# trainer.net
KiCad netlist of a schematic drawn in EAGLE
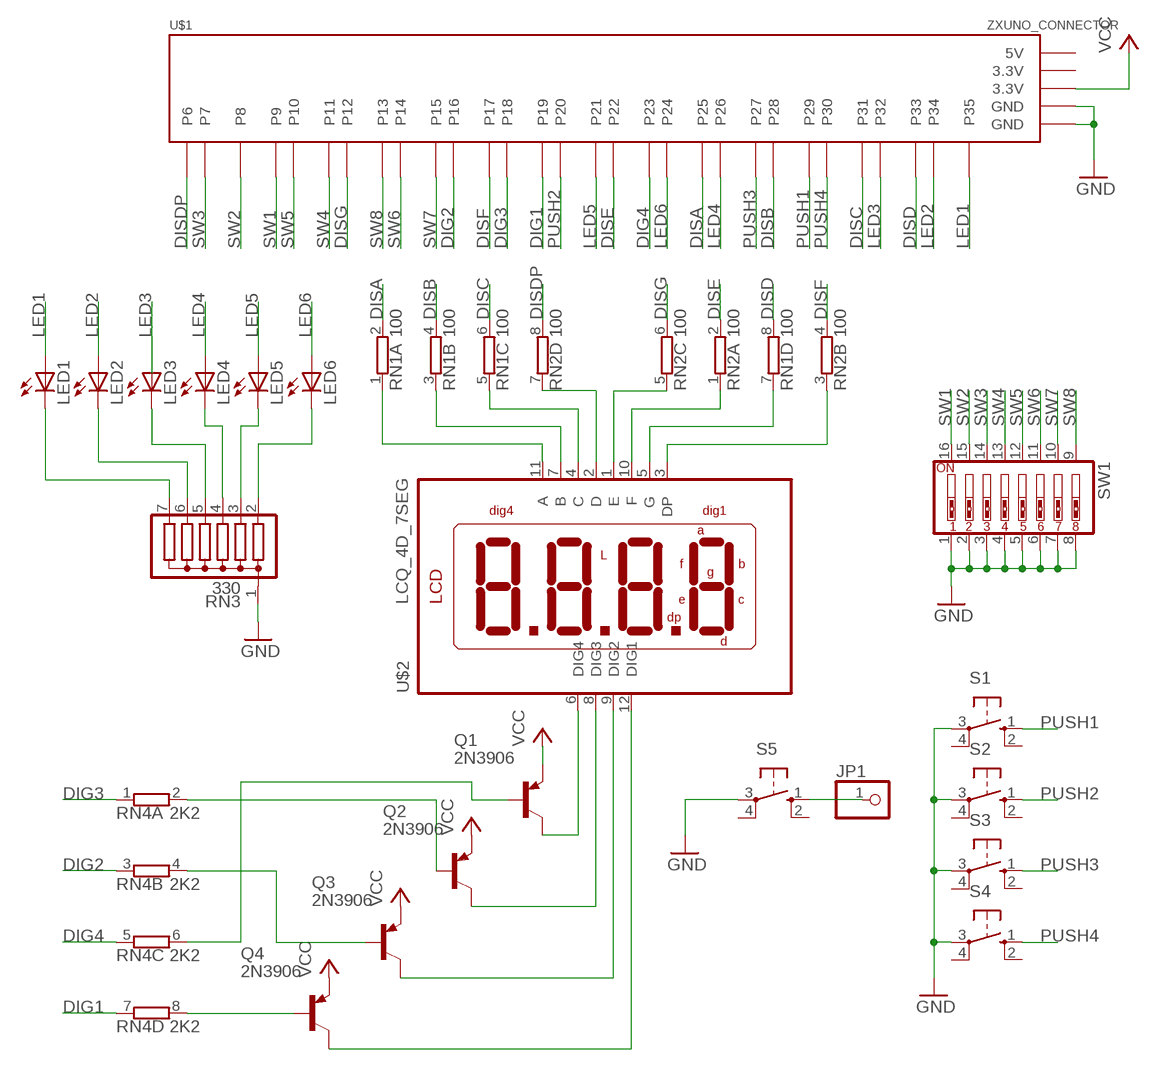
[diagram p0: schematic, sheet 1]

(export (version "E")
  (design (tool "Eeschema 10.0.6"))
  (components
    (comp (ref "JP1")
      (value "PINHD-1X1")
      (footprint "eagle-import:1X01")
      (libsource (lib "eagle-import") (part "PINHD-1X1"))
    )
    (comp (ref "LED1")
      (value "LED3MM")
      (footprint "eagle-import:LED3MM")
      (libsource (lib "eagle-import") (part "LED3MM"))
    )
    (comp (ref "LED2")
      (value "LED3MM")
      (footprint "eagle-import:LED3MM")
      (libsource (lib "eagle-import") (part "LED3MM"))
    )
    (comp (ref "LED3")
      (value "LED3MM")
      (footprint "eagle-import:LED3MM")
      (libsource (lib "eagle-import") (part "LED3MM"))
    )
    (comp (ref "LED4")
      (value "LED3MM")
      (footprint "eagle-import:LED3MM")
      (libsource (lib "eagle-import") (part "LED3MM"))
    )
    (comp (ref "LED5")
      (value "LED3MM")
      (footprint "eagle-import:LED3MM")
      (libsource (lib "eagle-import") (part "LED3MM"))
    )
    (comp (ref "LED6")
      (value "LED3MM")
      (footprint "eagle-import:LED3MM")
      (libsource (lib "eagle-import") (part "LED3MM"))
    )
    (comp (ref "Q1")
      (value "2N3906")
      (footprint "eagle-import:TO92")
      (libsource (lib "eagle-import") (part "2N3906"))
    )
    (comp (ref "Q2")
      (value "2N3906")
      (footprint "eagle-import:TO92")
      (libsource (lib "eagle-import") (part "2N3906"))
    )
    (comp (ref "Q3")
      (value "2N3906")
      (footprint "eagle-import:TO92")
      (libsource (lib "eagle-import") (part "2N3906"))
    )
    (comp (ref "Q4")
      (value "2N3906")
      (footprint "eagle-import:TO92")
      (libsource (lib "eagle-import") (part "2N3906"))
    )
    (comp (ref "RN1")
      (value "100")
      (footprint "eagle-import:SIL8")
      (libsource (lib "eagle-import") (part "E4R"))
    )
    (comp (ref "RN2")
      (value "100")
      (footprint "eagle-import:SIL8")
      (libsource (lib "eagle-import") (part "E4R"))
    )
    (comp (ref "RN3")
      (value "330")
      (footprint "eagle-import:SIL7")
      (libsource (lib "eagle-import") (part "G06R"))
    )
    (comp (ref "RN4")
      (value "2K2")
      (footprint "eagle-import:SIL8")
      (libsource (lib "eagle-import") (part "E4R"))
    )
    (comp (ref "S1")
      (value "10-XX")
      (footprint "eagle-import:B3F-10XX")
      (fields (field (name "MPN") "B3F-1000"))
      (libsource (lib "eagle-import") (part "10-XX"))
    )
    (comp (ref "S2")
      (value "10-XX")
      (footprint "eagle-import:B3F-10XX")
      (fields (field (name "MPN") "B3F-1000"))
      (libsource (lib "eagle-import") (part "10-XX"))
    )
    (comp (ref "S3")
      (value "10-XX")
      (footprint "eagle-import:B3F-10XX")
      (fields (field (name "MPN") "B3F-1000"))
      (libsource (lib "eagle-import") (part "10-XX"))
    )
    (comp (ref "S4")
      (value "10-XX")
      (footprint "eagle-import:B3F-10XX")
      (fields (field (name "MPN") "B3F-1000"))
      (libsource (lib "eagle-import") (part "10-XX"))
    )
    (comp (ref "S5")
      (value "10-XX")
      (footprint "eagle-import:B3F-10XX")
      (fields (field (name "MPN") "B3F-1000"))
      (libsource (lib "eagle-import") (part "10-XX"))
    )
    (comp (ref "SW1")
      (value "SW_DIP-8")
      (footprint "eagle-import:EDG-08")
      (libsource (lib "eagle-import") (part "SW_DIP-8"))
    )
    (comp (ref "U$1")
      (value "ZXUNO_CONNECTOR")
      (footprint "eagle-import:ZXUNO_CONNECTOR")
      (libsource (lib "eagle-import") (part "ZXUNO_CONNECTOR"))
    )
    (comp (ref "U$2")
      (value "LCQ_4D_7SEG")
      (footprint "eagle-import:LDQ_4D_7SEG")
      (libsource (lib "eagle-import") (part "LCQ_4D_7SEG"))
    )
  )
  (nets
    (net (code "1") (name "/3.3V") (class "Default")
      (node (ref "U$1") (pin "3.3V@1") (pinfunction "3.3V_3.3V@1") (pintype "power_in"))
    )
    (net (code "2") (name "/5V") (class "Default")
      (node (ref "U$1") (pin "5V") (pinfunction "5V_5V") (pintype "power_in"))
    )
    (net (code "3") (name "/DIG1") (class "Default")
      (node (ref "RN4") (pin "7") (pinfunction "1_7") (pintype "passive"))
      (node (ref "U$1") (pin "P19") (pinfunction "P19_P19") (pintype "bidirectional"))
    )
    (net (code "4") (name "/DIG2") (class "Default")
      (node (ref "RN4") (pin "3") (pinfunction "1_3") (pintype "passive"))
      (node (ref "U$1") (pin "P16") (pinfunction "P16_P16") (pintype "bidirectional"))
    )
    (net (code "5") (name "/DIG3") (class "Default")
      (node (ref "RN4") (pin "1") (pinfunction "1_1") (pintype "passive"))
      (node (ref "U$1") (pin "P18") (pinfunction "P18_P18") (pintype "bidirectional"))
    )
    (net (code "6") (name "/DIG4") (class "Default")
      (node (ref "RN4") (pin "5") (pinfunction "1_5") (pintype "passive"))
      (node (ref "U$1") (pin "P23") (pinfunction "P23_P23") (pintype "bidirectional"))
    )
    (net (code "7") (name "/DISA") (class "Default")
      (node (ref "RN1") (pin "2") (pinfunction "2_2") (pintype "passive"))
      (node (ref "U$1") (pin "P25") (pinfunction "P25_P25") (pintype "bidirectional"))
    )
    (net (code "8") (name "/DISB") (class "Default")
      (node (ref "RN1") (pin "4") (pinfunction "2_4") (pintype "passive"))
      (node (ref "U$1") (pin "P28") (pinfunction "P28_P28") (pintype "bidirectional"))
    )
    (net (code "9") (name "/DISC") (class "Default")
      (node (ref "RN1") (pin "6") (pinfunction "2_6") (pintype "passive"))
      (node (ref "U$1") (pin "P31") (pinfunction "P31_P31") (pintype "bidirectional"))
    )
    (net (code "10") (name "/DISD") (class "Default")
      (node (ref "RN1") (pin "8") (pinfunction "2_8") (pintype "passive"))
      (node (ref "U$1") (pin "P33") (pinfunction "P33_P33") (pintype "bidirectional"))
    )
    (net (code "11") (name "/DISDP") (class "Default")
      (node (ref "RN2") (pin "8") (pinfunction "2_8") (pintype "passive"))
      (node (ref "U$1") (pin "P6") (pinfunction "P6_P6") (pintype "bidirectional"))
    )
    (net (code "12") (name "/DISE") (class "Default")
      (node (ref "RN2") (pin "2") (pinfunction "2_2") (pintype "passive"))
      (node (ref "U$1") (pin "P22") (pinfunction "P22_P22") (pintype "bidirectional"))
    )
    (net (code "13") (name "/DISF") (class "Default")
      (node (ref "RN2") (pin "4") (pinfunction "2_4") (pintype "passive"))
      (node (ref "U$1") (pin "P17") (pinfunction "P17_P17") (pintype "bidirectional"))
    )
    (net (code "14") (name "/DISG") (class "Default")
      (node (ref "RN2") (pin "6") (pinfunction "2_6") (pintype "passive"))
      (node (ref "U$1") (pin "P12") (pinfunction "P12_P12") (pintype "bidirectional"))
    )
    (net (code "15") (name "/LED1") (class "Default")
      (node (ref "LED1") (pin "A") (pinfunction "A_A") (pintype "passive"))
      (node (ref "U$1") (pin "P35") (pinfunction "P35_P35") (pintype "bidirectional"))
    )
    (net (code "16") (name "/LED2") (class "Default")
      (node (ref "LED2") (pin "A") (pinfunction "A_A") (pintype "passive"))
      (node (ref "U$1") (pin "P34") (pinfunction "P34_P34") (pintype "bidirectional"))
    )
    (net (code "17") (name "/LED3") (class "Default")
      (node (ref "LED3") (pin "A") (pinfunction "A_A") (pintype "passive"))
      (node (ref "U$1") (pin "P32") (pinfunction "P32_P32") (pintype "bidirectional"))
    )
    (net (code "18") (name "/LED4") (class "Default")
      (node (ref "LED4") (pin "A") (pinfunction "A_A") (pintype "passive"))
      (node (ref "U$1") (pin "P26") (pinfunction "P26_P26") (pintype "bidirectional"))
    )
    (net (code "19") (name "/LED5") (class "Default")
      (node (ref "LED5") (pin "A") (pinfunction "A_A") (pintype "passive"))
      (node (ref "U$1") (pin "P21") (pinfunction "P21_P21") (pintype "bidirectional"))
    )
    (net (code "20") (name "/LED6") (class "Default")
      (node (ref "LED6") (pin "A") (pinfunction "A_A") (pintype "passive"))
      (node (ref "U$1") (pin "P24") (pinfunction "P24_P24") (pintype "bidirectional"))
    )
    (net (code "21") (name "/PUSH1") (class "Default")
      (node (ref "S1") (pin "1") (pinfunction "S_1") (pintype "passive"))
      (node (ref "U$1") (pin "P29") (pinfunction "P29_P29") (pintype "bidirectional"))
    )
    (net (code "22") (name "/PUSH2") (class "Default")
      (node (ref "S2") (pin "1") (pinfunction "S_1") (pintype "passive"))
      (node (ref "U$1") (pin "P20") (pinfunction "P20_P20") (pintype "bidirectional"))
    )
    (net (code "23") (name "/PUSH3") (class "Default")
      (node (ref "S3") (pin "1") (pinfunction "S_1") (pintype "passive"))
      (node (ref "U$1") (pin "P27") (pinfunction "P27_P27") (pintype "bidirectional"))
    )
    (net (code "24") (name "/PUSH4") (class "Default")
      (node (ref "S4") (pin "1") (pinfunction "S_1") (pintype "passive"))
      (node (ref "U$1") (pin "P30") (pinfunction "P30_P30") (pintype "bidirectional"))
    )
    (net (code "25") (name "/SW1") (class "Default")
      (node (ref "SW1") (pin "16") (pinfunction "16_16") (pintype "passive"))
      (node (ref "U$1") (pin "P9") (pinfunction "P9_P9") (pintype "bidirectional"))
    )
    (net (code "26") (name "/SW2") (class "Default")
      (node (ref "SW1") (pin "15") (pinfunction "15_15") (pintype "passive"))
      (node (ref "U$1") (pin "P8") (pinfunction "P8_P8") (pintype "bidirectional"))
    )
    (net (code "27") (name "/SW3") (class "Default")
      (node (ref "SW1") (pin "14") (pinfunction "14_14") (pintype "passive"))
      (node (ref "U$1") (pin "P7") (pinfunction "P7_P7") (pintype "bidirectional"))
    )
    (net (code "28") (name "/SW4") (class "Default")
      (node (ref "SW1") (pin "13") (pinfunction "13_13") (pintype "passive"))
      (node (ref "U$1") (pin "P11") (pinfunction "P11_P11") (pintype "bidirectional"))
    )
    (net (code "29") (name "/SW5") (class "Default")
      (node (ref "SW1") (pin "12") (pinfunction "12_12") (pintype "passive"))
      (node (ref "U$1") (pin "P10") (pinfunction "P10_P10") (pintype "bidirectional"))
    )
    (net (code "30") (name "/SW6") (class "Default")
      (node (ref "SW1") (pin "11") (pinfunction "11_11") (pintype "passive"))
      (node (ref "U$1") (pin "P14") (pinfunction "P14_P14") (pintype "bidirectional"))
    )
    (net (code "31") (name "/SW7") (class "Default")
      (node (ref "SW1") (pin "10") (pinfunction "10_10") (pintype "passive"))
      (node (ref "U$1") (pin "P15") (pinfunction "P15_P15") (pintype "bidirectional"))
    )
    (net (code "32") (name "/SW8") (class "Default")
      (node (ref "SW1") (pin "9") (pinfunction "9_9") (pintype "passive"))
      (node (ref "U$1") (pin "P13") (pinfunction "P13_P13") (pintype "bidirectional"))
    )
    (net (code "33") (name "GND") (class "Default")
      (node (ref "RN3") (pin "1") (pinfunction "1_1") (pintype "passive"))
      (node (ref "S1") (pin "3") (pinfunction "P_3") (pintype "passive"))
      (node (ref "S2") (pin "3") (pinfunction "P_3") (pintype "passive"))
      (node (ref "S3") (pin "3") (pinfunction "P_3") (pintype "passive"))
      (node (ref "S4") (pin "3") (pinfunction "P_3") (pintype "passive"))
      (node (ref "S5") (pin "3") (pinfunction "P_3") (pintype "passive"))
      (node (ref "SW1") (pin "1") (pinfunction "1_1") (pintype "passive"))
      (node (ref "SW1") (pin "2") (pinfunction "2_2") (pintype "passive"))
      (node (ref "SW1") (pin "3") (pinfunction "3_3") (pintype "passive"))
      (node (ref "SW1") (pin "4") (pinfunction "4_4") (pintype "passive"))
      (node (ref "SW1") (pin "5") (pinfunction "5_5") (pintype "passive"))
      (node (ref "SW1") (pin "6") (pinfunction "6_6") (pintype "passive"))
      (node (ref "SW1") (pin "7") (pinfunction "7_7") (pintype "passive"))
      (node (ref "SW1") (pin "8") (pinfunction "8_8") (pintype "passive"))
      (node (ref "U$1") (pin "GND@1") (pinfunction "GND_GND@1") (pintype "power_in"))
      (node (ref "U$1") (pin "GND@2") (pinfunction "GND_GND@2") (pintype "power_in"))
    )
    (net (code "34") (name "Net-(LED1-C)") (class "Default")
      (node (ref "LED1") (pin "K") (pinfunction "C_K") (pintype "passive"))
      (node (ref "RN3") (pin "7") (pinfunction "7_7") (pintype "passive"))
    )
    (net (code "35") (name "Net-(LED2-C)") (class "Default")
      (node (ref "LED2") (pin "K") (pinfunction "C_K") (pintype "passive"))
      (node (ref "RN3") (pin "6") (pinfunction "6_6") (pintype "passive"))
    )
    (net (code "36") (name "Net-(LED3-C)") (class "Default")
      (node (ref "LED3") (pin "K") (pinfunction "C_K") (pintype "passive"))
      (node (ref "RN3") (pin "5") (pinfunction "5_5") (pintype "passive"))
    )
    (net (code "37") (name "Net-(LED4-C)") (class "Default")
      (node (ref "LED4") (pin "K") (pinfunction "C_K") (pintype "passive"))
      (node (ref "RN3") (pin "4") (pinfunction "4_4") (pintype "passive"))
    )
    (net (code "38") (name "Net-(LED5-C)") (class "Default")
      (node (ref "LED5") (pin "K") (pinfunction "C_K") (pintype "passive"))
      (node (ref "RN3") (pin "3") (pinfunction "3_3") (pintype "passive"))
    )
    (net (code "39") (name "Net-(LED6-C)") (class "Default")
      (node (ref "LED6") (pin "K") (pinfunction "C_K") (pintype "passive"))
      (node (ref "RN3") (pin "2") (pinfunction "2_2") (pintype "passive"))
    )
    (net (code "40") (name "Net-(Q1-B)") (class "Default")
      (node (ref "Q1") (pin "2") (pinfunction "B_2") (pintype "passive"))
      (node (ref "RN4") (pin "6") (pinfunction "2_6") (pintype "passive"))
    )
    (net (code "41") (name "Net-(Q1-C)") (class "Default")
      (node (ref "Q1") (pin "1") (pinfunction "C_1") (pintype "passive"))
      (node (ref "U$2") (pin "6") (pinfunction "DIG4_6") (pintype "input"))
    )
    (net (code "42") (name "Net-(Q2-B)") (class "Default")
      (node (ref "Q2") (pin "2") (pinfunction "B_2") (pintype "passive"))
      (node (ref "RN4") (pin "2") (pinfunction "2_2") (pintype "passive"))
    )
    (net (code "43") (name "Net-(Q2-C)") (class "Default")
      (node (ref "Q2") (pin "1") (pinfunction "C_1") (pintype "passive"))
      (node (ref "U$2") (pin "8") (pinfunction "DIG3_8") (pintype "input"))
    )
    (net (code "44") (name "Net-(Q3-B)") (class "Default")
      (node (ref "Q3") (pin "2") (pinfunction "B_2") (pintype "passive"))
      (node (ref "RN4") (pin "4") (pinfunction "2_4") (pintype "passive"))
    )
    (net (code "45") (name "Net-(Q3-C)") (class "Default")
      (node (ref "Q3") (pin "1") (pinfunction "C_1") (pintype "passive"))
      (node (ref "U$2") (pin "9") (pinfunction "DIG2_9") (pintype "input"))
    )
    (net (code "46") (name "Net-(Q4-B)") (class "Default")
      (node (ref "Q4") (pin "2") (pinfunction "B_2") (pintype "passive"))
      (node (ref "RN4") (pin "8") (pinfunction "2_8") (pintype "passive"))
    )
    (net (code "47") (name "Net-(Q4-C)") (class "Default")
      (node (ref "Q4") (pin "1") (pinfunction "C_1") (pintype "passive"))
      (node (ref "U$2") (pin "12") (pinfunction "DIG1_12") (pintype "input"))
    )
    (net (code "48") (name "Net-(RN1B-1)") (class "Default")
      (node (ref "RN1") (pin "3") (pinfunction "1_3") (pintype "passive"))
      (node (ref "U$2") (pin "7") (pinfunction "B_7") (pintype "input"))
    )
    (net (code "49") (name "Net-(RN1C-1)") (class "Default")
      (node (ref "RN1") (pin "5") (pinfunction "1_5") (pintype "passive"))
      (node (ref "U$2") (pin "4") (pinfunction "C_4") (pintype "input"))
    )
    (net (code "50") (name "Net-(RN1D-1)") (class "Default")
      (node (ref "RN1") (pin "7") (pinfunction "1_7") (pintype "passive"))
      (node (ref "U$2") (pin "5") (pinfunction "G_5") (pintype "input"))
    )
    (net (code "51") (name "Net-(RN2B-1)") (class "Default")
      (node (ref "RN2") (pin "3") (pinfunction "1_3") (pintype "passive"))
      (node (ref "U$2") (pin "3") (pinfunction "DP_3") (pintype "input"))
    )
    (net (code "52") (name "Net-(RN2C-1)") (class "Default")
      (node (ref "RN2") (pin "5") (pinfunction "1_5") (pintype "passive"))
      (node (ref "U$2") (pin "1") (pinfunction "E_1") (pintype "input"))
    )
    (net (code "53") (name "Net-(RN2D-1)") (class "Default")
      (node (ref "RN2") (pin "7") (pinfunction "1_7") (pintype "passive"))
      (node (ref "U$2") (pin "2") (pinfunction "D_2") (pintype "input"))
    )
    (net (code "54") (name "Net-(S5-S)") (class "Default")
      (node (ref "JP1") (pin "1") (pinfunction "1_1") (pintype "passive"))
      (node (ref "S5") (pin "1") (pinfunction "S_1") (pintype "passive"))
    )
    (net (code "55") (name "Net-(U$2-A)") (class "Default")
      (node (ref "RN1") (pin "1") (pinfunction "1_1") (pintype "passive"))
      (node (ref "U$2") (pin "11") (pinfunction "A_11") (pintype "input"))
    )
    (net (code "56") (name "Net-(U$2-F)") (class "Default")
      (node (ref "RN2") (pin "1") (pinfunction "1_1") (pintype "passive"))
      (node (ref "U$2") (pin "10") (pinfunction "F_10") (pintype "input"))
    )
    (net (code "57") (name "VCC") (class "Default")
      (node (ref "Q1") (pin "3") (pinfunction "E_3") (pintype "passive"))
      (node (ref "Q2") (pin "3") (pinfunction "E_3") (pintype "passive"))
      (node (ref "Q3") (pin "3") (pinfunction "E_3") (pintype "passive"))
      (node (ref "Q4") (pin "3") (pinfunction "E_3") (pintype "passive"))
      (node (ref "U$1") (pin "3.3V@2") (pinfunction "3.3V_3.3V@2") (pintype "power_in"))
    )
    (net (code "58") (name "unconnected-(S1-P1-Pad4)") (class "Default")
      (node (ref "S1") (pin "4") (pinfunction "P1_4") (pintype "passive"))
    )
    (net (code "59") (name "unconnected-(S1-S1-Pad2)") (class "Default")
      (node (ref "S1") (pin "2") (pinfunction "S1_2") (pintype "passive"))
    )
    (net (code "60") (name "unconnected-(S2-P1-Pad4)") (class "Default")
      (node (ref "S2") (pin "4") (pinfunction "P1_4") (pintype "passive"))
    )
    (net (code "61") (name "unconnected-(S2-S1-Pad2)") (class "Default")
      (node (ref "S2") (pin "2") (pinfunction "S1_2") (pintype "passive"))
    )
    (net (code "62") (name "unconnected-(S3-P1-Pad4)") (class "Default")
      (node (ref "S3") (pin "4") (pinfunction "P1_4") (pintype "passive"))
    )
    (net (code "63") (name "unconnected-(S3-S1-Pad2)") (class "Default")
      (node (ref "S3") (pin "2") (pinfunction "S1_2") (pintype "passive"))
    )
    (net (code "64") (name "unconnected-(S4-P1-Pad4)") (class "Default")
      (node (ref "S4") (pin "4") (pinfunction "P1_4") (pintype "passive"))
    )
    (net (code "65") (name "unconnected-(S4-S1-Pad2)") (class "Default")
      (node (ref "S4") (pin "2") (pinfunction "S1_2") (pintype "passive"))
    )
    (net (code "66") (name "unconnected-(S5-P1-Pad4)") (class "Default")
      (node (ref "S5") (pin "4") (pinfunction "P1_4") (pintype "passive"))
    )
    (net (code "67") (name "unconnected-(S5-S1-Pad2)") (class "Default")
      (node (ref "S5") (pin "2") (pinfunction "S1_2") (pintype "passive"))
    )
  )
)
